# ATM90E32AS.net
KiCad netlist of a schematic drawn in Altium Designer
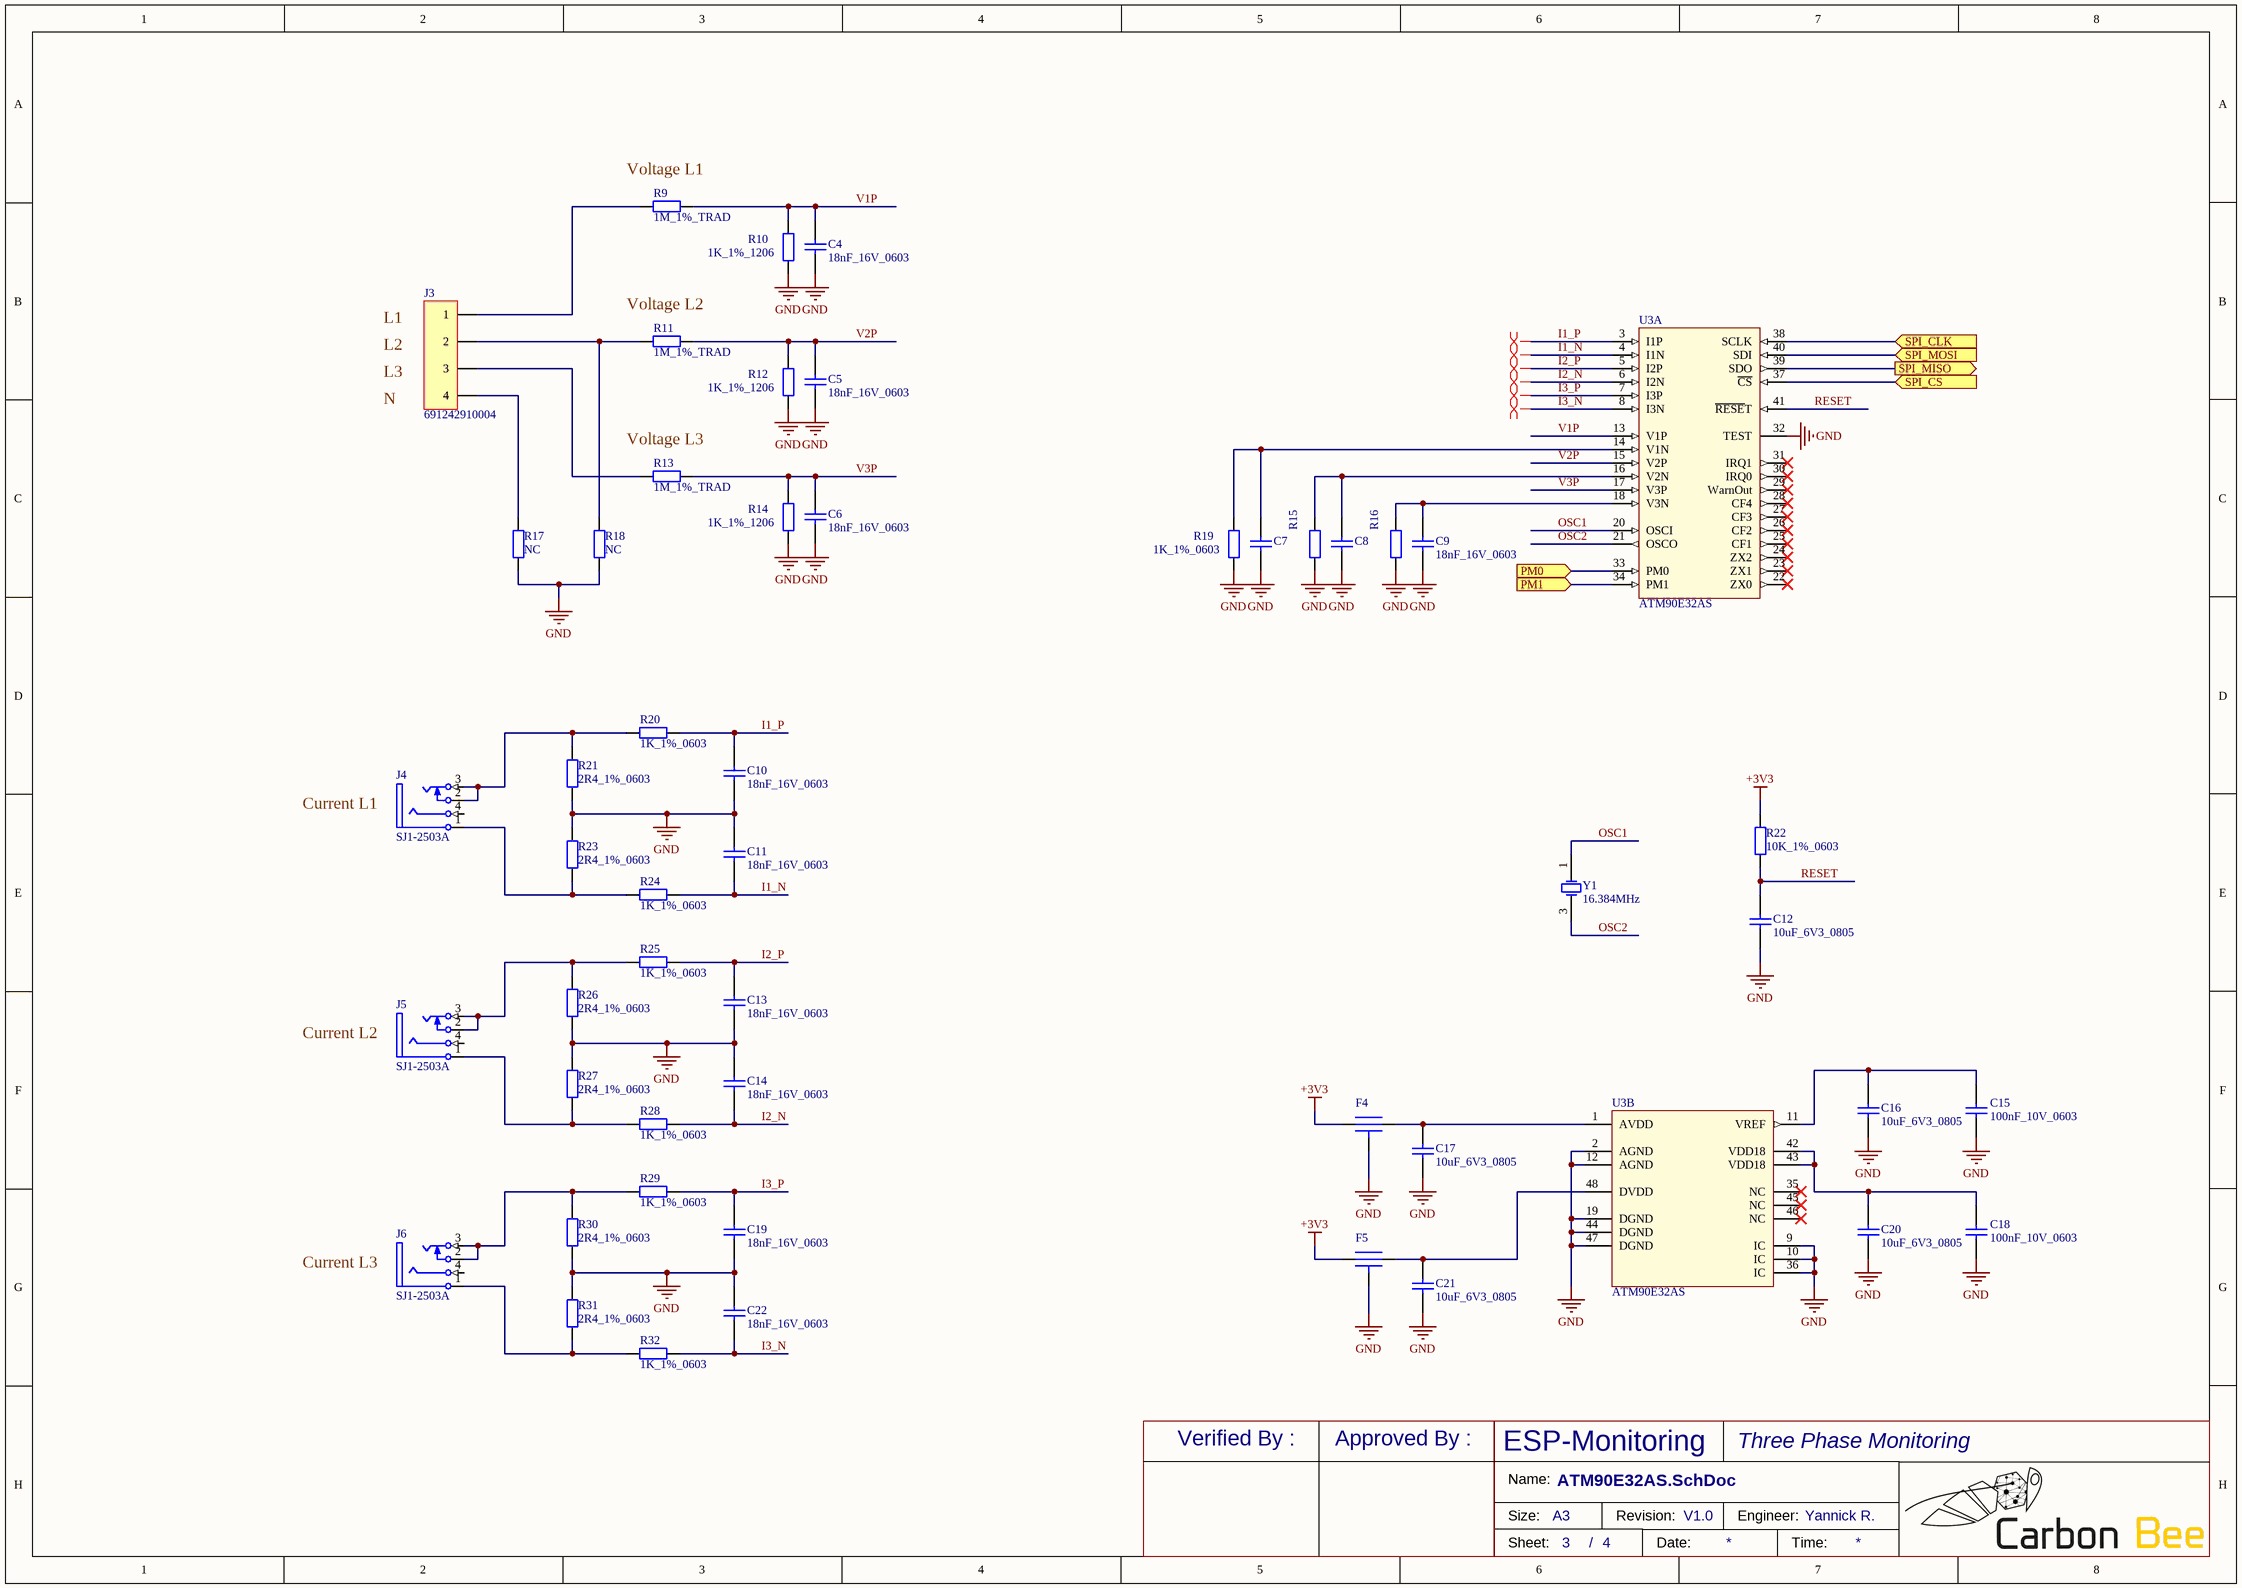
[diagram p0: ATM90E32AS.SchDoc]

(export (version "E")
  (design (tool "Eeschema 10.0.6"))
  (components
    (comp (ref "C4")
      (value "18nF_16V_0603")
      (footprint "C0603")
      (description "Capacitor")
      (fields (field (name "MF") "MULTICOMP") (field (name "MPN") "MC0603B183K160CT"))
      (libsource (lib "Common") (part "Cap"))
    )
    (comp (ref "C5")
      (value "18nF_16V_0603")
      (footprint "C0603")
      (description "Capacitor")
      (fields (field (name "MF") "MULTICOMP") (field (name "MPN") "MC0603B183K160CT"))
      (libsource (lib "Common") (part "Cap"))
    )
    (comp (ref "C6")
      (value "18nF_16V_0603")
      (footprint "C0603")
      (description "Capacitor")
      (fields (field (name "MF") "MULTICOMP") (field (name "MPN") "MC0603B183K160CT"))
      (libsource (lib "Common") (part "Cap"))
    )
    (comp (ref "C7")
      (value "18nF_16V_0603")
      (footprint "C0603")
      (description "Capacitor")
      (fields (field (name "MF") "MULTICOMP") (field (name "MPN") "MC0603B183K160CT"))
      (libsource (lib "Common") (part "Cap"))
    )
    (comp (ref "C8")
      (value "18nF_16V_0603")
      (footprint "C0603")
      (description "Capacitor")
      (fields (field (name "MF") "MULTICOMP") (field (name "MPN") "MC0603B183K160CT"))
      (libsource (lib "Common") (part "Cap"))
    )
    (comp (ref "C9")
      (value "18nF_16V_0603")
      (footprint "C0603")
      (description "Capacitor")
      (fields (field (name "MF") "MULTICOMP") (field (name "MPN") "MC0603B183K160CT"))
      (libsource (lib "Common") (part "Cap"))
    )
    (comp (ref "C10")
      (value "18nF_16V_0603")
      (footprint "C0603")
      (description "Capacitor")
      (fields (field (name "MF") "MULTICOMP") (field (name "MPN") "MC0603B183K160CT"))
      (libsource (lib "Common") (part "Cap"))
    )
    (comp (ref "C11")
      (value "18nF_16V_0603")
      (footprint "C0603")
      (description "Capacitor")
      (fields (field (name "MF") "MULTICOMP") (field (name "MPN") "MC0603B183K160CT"))
      (libsource (lib "Common") (part "Cap"))
    )
    (comp (ref "C12")
      (value "10uF_6V3_0805")
      (footprint "Common:C0805")
      (description "Capacitor")
      (fields (field (name "MF") " MULTICOMP") (field (name "MPN") "MCTT21X106M6R3CT"))
      (libsource (lib "Common") (part "Cap"))
    )
    (comp (ref "C13")
      (value "18nF_16V_0603")
      (footprint "C0603")
      (description "Capacitor")
      (fields (field (name "MF") "MULTICOMP") (field (name "MPN") "MC0603B183K160CT"))
      (libsource (lib "Common") (part "Cap"))
    )
    (comp (ref "C14")
      (value "18nF_16V_0603")
      (footprint "C0603")
      (description "Capacitor")
      (fields (field (name "MF") "MULTICOMP") (field (name "MPN") "MC0603B183K160CT"))
      (libsource (lib "Common") (part "Cap"))
    )
    (comp (ref "C15")
      (value "100nF_10V_0603")
      (footprint "C0603")
      (description "Capacitor")
      (fields (field (name "MF") "MULTICOMP") (field (name "MPN") "MC0603B104K100CT"))
      (libsource (lib "Common") (part "Cap"))
    )
    (comp (ref "C16")
      (value "10uF_6V3_0805")
      (footprint "Common:C0805")
      (description "Capacitor")
      (fields (field (name "MF") " MULTICOMP") (field (name "MPN") "MCTT21X106M6R3CT"))
      (libsource (lib "Common") (part "Cap"))
    )
    (comp (ref "C17")
      (value "10uF_6V3_0805")
      (footprint "Common:C0805")
      (description "Capacitor")
      (fields (field (name "MF") " MULTICOMP") (field (name "MPN") "MCTT21X106M6R3CT"))
      (libsource (lib "Common") (part "Cap"))
    )
    (comp (ref "C18")
      (value "100nF_10V_0603")
      (footprint "C0603")
      (description "Capacitor")
      (fields (field (name "MF") "MULTICOMP") (field (name "MPN") "MC0603B104K100CT"))
      (libsource (lib "Common") (part "Cap"))
    )
    (comp (ref "C19")
      (value "18nF_16V_0603")
      (footprint "C0603")
      (description "Capacitor")
      (fields (field (name "MF") "MULTICOMP") (field (name "MPN") "MC0603B183K160CT"))
      (libsource (lib "Common") (part "Cap"))
    )
    (comp (ref "C20")
      (value "10uF_6V3_0805")
      (footprint "Common:C0805")
      (description "Capacitor")
      (fields (field (name "MF") " MULTICOMP") (field (name "MPN") "MCTT21X106M6R3CT"))
      (libsource (lib "Common") (part "Cap"))
    )
    (comp (ref "C21")
      (value "10uF_6V3_0805")
      (footprint "Common:C0805")
      (description "Capacitor")
      (fields (field (name "MF") " MULTICOMP") (field (name "MPN") "MCTT21X106M6R3CT"))
      (libsource (lib "Common") (part "Cap"))
    )
    (comp (ref "C22")
      (value "18nF_16V_0603")
      (footprint "C0603")
      (description "Capacitor")
      (fields (field (name "MF") "MULTICOMP") (field (name "MPN") "MC0603B183K160CT"))
      (libsource (lib "Common") (part "Cap"))
    )
    (comp (ref "F4")
      (value "EMI")
      (footprint "EMIFIL_0603")
      (description "FILTER CAP 0.1UF 2A 16V 0603")
      (fields (field (name "MF") "MURATA") (field (name "MPN") "NFM18PC104R1C3D"))
      (libsource (lib "Common") (part "EMIFIL_0603"))
    )
    (comp (ref "F5")
      (value "EMI")
      (footprint "EMIFIL_0603")
      (description "FILTER CAP 0.1UF 2A 16V 0603")
      (fields (field (name "MF") "MURATA") (field (name "MPN") "NFM18PC104R1C3D"))
      (libsource (lib "Common") (part "EMIFIL_0603"))
    )
    (comp (ref "J3")
      (value "691242910004")
      (footprint "691242910004")
      (description "Horizontal Cable Entry with Rising Cage Clamp, Serie 2429 - 7.5 mm")
      (fields (field (name "MF") "Wurth Elektronik"))
      (libsource (lib "WE_WR-TBL_Rising Cage System_7.50 mm_rev15b") (part "691242910004"))
    )
    (comp (ref "J4")
      (value "SJ1-2503A")
      (footprint "SJ1-2503A")
      (description "Jack Socket, 1/4\" [6.5mm], Thru-Hole, Vertical, 3-Conductor with Tip closed & Ring open")
      (fields (field (name "MF") "CUI Inc."))
      (libsource (lib "Miscellaneous Connectors") (part "Phonejack3 TN"))
    )
    (comp (ref "J5")
      (value "SJ1-2503A")
      (footprint "SJ1-2503A")
      (description "Jack Socket, 1/4\" [6.5mm], Thru-Hole, Vertical, 3-Conductor with Tip closed & Ring open")
      (fields (field (name "MF") "CUI Inc."))
      (libsource (lib "Miscellaneous Connectors") (part "Phonejack3 TN"))
    )
    (comp (ref "J6")
      (value "SJ1-2503A")
      (footprint "SJ1-2503A")
      (description "Jack Socket, 1/4\" [6.5mm], Thru-Hole, Vertical, 3-Conductor with Tip closed & Ring open")
      (fields (field (name "MF") "CUI Inc."))
      (libsource (lib "Miscellaneous Connectors") (part "Phonejack3 TN"))
    )
    (comp (ref "R9")
      (value "1M_1%_TRAD")
      (footprint "AXIAL-0.3")
      (description "Resistor")
      (fields (field (name "MF") "TT ELECTRONICS / WELWYN") (field (name "MPN") "MH25-1MJI"))
      (libsource (lib "") (part "RES_1"))
    )
    (comp (ref "R10")
      (value "1K_1%_1206")
      (footprint "R1206")
      (description "Resistor")
      (fields (field (name "MF") "MULTICOMP") (field (name "MPN") "MC0125W120651K"))
      (libsource (lib "") (part "RES_2"))
    )
    (comp (ref "R11")
      (value "1M_1%_TRAD")
      (footprint "AXIAL-0.3")
      (description "Resistor")
      (fields (field (name "MF") "TT ELECTRONICS / WELWYN") (field (name "MPN") "MH25-1MJI"))
      (libsource (lib "") (part "RES_1"))
    )
    (comp (ref "R12")
      (value "1K_1%_1206")
      (footprint "R1206")
      (description "Resistor")
      (fields (field (name "MF") "MULTICOMP") (field (name "MPN") "MC0125W120651K"))
      (libsource (lib "") (part "RES_2"))
    )
    (comp (ref "R13")
      (value "1M_1%_TRAD")
      (footprint "AXIAL-0.3")
      (description "Resistor")
      (fields (field (name "MF") "TT ELECTRONICS / WELWYN") (field (name "MPN") "MH25-1MJI"))
      (libsource (lib "") (part "RES_1"))
    )
    (comp (ref "R14")
      (value "1K_1%_1206")
      (footprint "R1206")
      (description "Resistor")
      (fields (field (name "MF") "MULTICOMP") (field (name "MPN") "MC0125W120651K"))
      (libsource (lib "") (part "RES_2"))
    )
    (comp (ref "R15")
      (value "1K_1%_0603")
      (footprint "R0603")
      (description "Resistor")
      (fields (field (name "MF") "VISHAY") (field (name "MPN") "CRCW06031K00FKEA"))
      (libsource (lib "") (part "RES_2"))
    )
    (comp (ref "R16")
      (value "1K_1%_0603")
      (footprint "R0603")
      (description "Resistor")
      (fields (field (name "MF") "VISHAY") (field (name "MPN") "CRCW06031K00FKEA"))
      (libsource (lib "") (part "RES_2"))
    )
    (comp (ref "R17")
      (value "NC")
      (footprint "AXIAL-0.4")
      (description "Resistor")
      (libsource (lib "") (part "RES_3"))
    )
    (comp (ref "R18")
      (value "NC")
      (footprint "AXIAL-0.4")
      (description "Resistor")
      (libsource (lib "") (part "RES_3"))
    )
    (comp (ref "R19")
      (value "1K_1%_0603")
      (footprint "R0603")
      (description "Resistor")
      (fields (field (name "MF") "VISHAY") (field (name "MPN") "CRCW06031K00FKEA"))
      (libsource (lib "") (part "RES_2"))
    )
    (comp (ref "R20")
      (value "1K_1%_0603")
      (footprint "R0603")
      (description "Resistor")
      (fields (field (name "MF") "VISHAY") (field (name "MPN") "CRCW06031K00FKEA"))
      (libsource (lib "") (part "RES_1"))
    )
    (comp (ref "R21")
      (value "2R4_1%_0603")
      (footprint "R0603")
      (description "Resistor")
      (fields (field (name "MF") "WALSIN") (field (name "MPN") "WR06W2R40FTL"))
      (libsource (lib "") (part "RES_3"))
    )
    (comp (ref "R22")
      (value "10K_1%_0603")
      (footprint "R0603")
      (description "Resistor")
      (fields (field (name "MPN") "MCWR06X1002FTL") (field (name "MF") "MULTICOMP"))
      (libsource (lib "Common") (part "RES"))
    )
    (comp (ref "R23")
      (value "2R4_1%_0603")
      (footprint "R0603")
      (description "Resistor")
      (fields (field (name "MF") "WALSIN") (field (name "MPN") "WR06W2R40FTL"))
      (libsource (lib "Common") (part "RES"))
    )
    (comp (ref "R24")
      (value "1K_1%_0603")
      (footprint "R0603")
      (description "Resistor")
      (fields (field (name "MF") "VISHAY") (field (name "MPN") "CRCW06031K00FKEA"))
      (libsource (lib "") (part "RES_3"))
    )
    (comp (ref "R25")
      (value "1K_1%_0603")
      (footprint "R0603")
      (description "Resistor")
      (fields (field (name "MF") "VISHAY") (field (name "MPN") "CRCW06031K00FKEA"))
      (libsource (lib "") (part "RES_1"))
    )
    (comp (ref "R26")
      (value "2R4_1%_0603")
      (footprint "R0603")
      (description "Resistor")
      (fields (field (name "MF") "WALSIN") (field (name "MPN") "WR06W2R40FTL"))
      (libsource (lib "") (part "RES_3"))
    )
    (comp (ref "R27")
      (value "2R4_1%_0603")
      (footprint "R0603")
      (description "Resistor")
      (fields (field (name "MF") "WALSIN") (field (name "MPN") "WR06W2R40FTL"))
      (libsource (lib "Common") (part "RES"))
    )
    (comp (ref "R28")
      (value "1K_1%_0603")
      (footprint "R0603")
      (description "Resistor")
      (fields (field (name "MF") "VISHAY") (field (name "MPN") "CRCW06031K00FKEA"))
      (libsource (lib "") (part "RES_3"))
    )
    (comp (ref "R29")
      (value "1K_1%_0603")
      (footprint "R0603")
      (description "Resistor")
      (fields (field (name "MF") "VISHAY") (field (name "MPN") "CRCW06031K00FKEA"))
      (libsource (lib "") (part "RES_1"))
    )
    (comp (ref "R30")
      (value "2R4_1%_0603")
      (footprint "R0603")
      (description "Resistor")
      (fields (field (name "MF") "WALSIN") (field (name "MPN") "WR06W2R40FTL"))
      (libsource (lib "") (part "RES_3"))
    )
    (comp (ref "R31")
      (value "2R4_1%_0603")
      (footprint "R0603")
      (description "Resistor")
      (fields (field (name "MF") "WALSIN") (field (name "MPN") "WR06W2R40FTL"))
      (libsource (lib "Common") (part "RES"))
    )
    (comp (ref "R32")
      (value "1K_1%_0603")
      (footprint "R0603")
      (description "Resistor")
      (fields (field (name "MF") "VISHAY") (field (name "MPN") "CRCW06031K00FKEA"))
      (libsource (lib "") (part "RES_3"))
    )
    (comp (ref "U3")
      (value "ATM90E32AS")
      (footprint "TQFP48")
      (description "Enhanced Poly-Phase High-Performance Wide-Span Energy Metering IC")
      (fields (field (name "MF") "MICROCHIP") (field (name "MPN") "ATM90E32AS-AU-R"))
      (libsource (lib "Common") (part "ATM90E32AS"))
    )
    (comp (ref "Y1")
      (value "16.384MHz")
      (footprint "OSC_3.2X2.5")
      (description "Crystal Oscillator")
      (fields (field (name "MF") "MULTICOMP") (field (name "MPN") "MCSJK-7U-16.384-10-30-80-B-30"))
      (libsource (lib "Miscellaneous Devices") (part "XTAL"))
    )
  )
  (nets
    (net (code "1") (name "+3V3") (class "Default")
      (node (ref "F4") (pin "2") (pinfunction "2_2") (pintype "passive"))
      (node (ref "F5") (pin "2") (pinfunction "2_2") (pintype "passive"))
      (node (ref "R22") (pin "2") (pinfunction "2_2") (pintype "passive"))
    )
    (net (code "2") (name "/I1_N") (class "Default")
      (node (ref "C11") (pin "2") (pinfunction "2_2") (pintype "passive"))
      (node (ref "R24") (pin "1") (pinfunction "1_1") (pintype "passive"))
      (node (ref "U3") (pin "4") (pinfunction "I1N_4") (pintype "input"))
    )
    (net (code "3") (name "/I1_P") (class "Default")
      (node (ref "C10") (pin "2") (pinfunction "2_2") (pintype "passive"))
      (node (ref "R20") (pin "1") (pinfunction "1_1") (pintype "passive"))
      (node (ref "U3") (pin "3") (pinfunction "I1P_3") (pintype "input"))
    )
    (net (code "4") (name "/I2_N") (class "Default")
      (node (ref "C14") (pin "2") (pinfunction "2_2") (pintype "passive"))
      (node (ref "R28") (pin "1") (pinfunction "1_1") (pintype "passive"))
      (node (ref "U3") (pin "6") (pinfunction "I2N_6") (pintype "input"))
    )
    (net (code "5") (name "/I2_P") (class "Default")
      (node (ref "C13") (pin "2") (pinfunction "2_2") (pintype "passive"))
      (node (ref "R25") (pin "1") (pinfunction "1_1") (pintype "passive"))
      (node (ref "U3") (pin "5") (pinfunction "I2P_5") (pintype "input"))
    )
    (net (code "6") (name "/I3_N") (class "Default")
      (node (ref "C22") (pin "2") (pinfunction "2_2") (pintype "passive"))
      (node (ref "R32") (pin "1") (pinfunction "1_1") (pintype "passive"))
      (node (ref "U3") (pin "8") (pinfunction "I3N_8") (pintype "input"))
    )
    (net (code "7") (name "/I3_P") (class "Default")
      (node (ref "C19") (pin "2") (pinfunction "2_2") (pintype "passive"))
      (node (ref "R29") (pin "1") (pinfunction "1_1") (pintype "passive"))
      (node (ref "U3") (pin "7") (pinfunction "I3P_7") (pintype "input"))
    )
    (net (code "8") (name "/OSC1") (class "Default")
      (node (ref "U3") (pin "20") (pinfunction "OSCI_20") (pintype "input"))
      (node (ref "Y1") (pin "1") (pinfunction "OSC1_1") (pintype "passive"))
    )
    (net (code "9") (name "/OSC2") (class "Default")
      (node (ref "U3") (pin "21") (pinfunction "OSCO_21") (pintype "output"))
      (node (ref "Y1") (pin "3") (pinfunction "OSC2_3") (pintype "passive"))
    )
    (net (code "10") (name "/PM0") (class "Default")
      (node (ref "U3") (pin "33") (pinfunction "PM0_33") (pintype "input"))
    )
    (net (code "11") (name "/PM1") (class "Default")
      (node (ref "U3") (pin "34") (pinfunction "PM1_34") (pintype "input"))
    )
    (net (code "12") (name "/RESET") (class "Default")
      (node (ref "C12") (pin "2") (pinfunction "2_2") (pintype "passive"))
      (node (ref "R22") (pin "1") (pinfunction "1_1") (pintype "passive"))
      (node (ref "U3") (pin "41") (pinfunction "~{RESE}T_41") (pintype "input"))
    )
    (net (code "13") (name "/SPI_CLK") (class "Default")
      (node (ref "U3") (pin "38") (pinfunction "SCLK_38") (pintype "input"))
    )
    (net (code "14") (name "/SPI_CS") (class "Default")
      (node (ref "U3") (pin "37") (pinfunction "~{CS}_37") (pintype "input"))
    )
    (net (code "15") (name "/SPI_MISO") (class "Default")
      (node (ref "U3") (pin "39") (pinfunction "SDO_39") (pintype "output"))
    )
    (net (code "16") (name "/SPI_MOSI") (class "Default")
      (node (ref "U3") (pin "40") (pinfunction "SDI_40") (pintype "input"))
    )
    (net (code "17") (name "/V1P") (class "Default")
      (node (ref "C4") (pin "2") (pinfunction "2_2") (pintype "passive"))
      (node (ref "R10") (pin "2") (pinfunction "2_2") (pintype "passive"))
      (node (ref "R9") (pin "1") (pinfunction "1_1") (pintype "passive"))
      (node (ref "U3") (pin "13") (pinfunction "V1P_13") (pintype "input"))
    )
    (net (code "18") (name "/V2P") (class "Default")
      (node (ref "C5") (pin "2") (pinfunction "2_2") (pintype "passive"))
      (node (ref "R11") (pin "1") (pinfunction "1_1") (pintype "passive"))
      (node (ref "R12") (pin "2") (pinfunction "2_2") (pintype "passive"))
      (node (ref "U3") (pin "15") (pinfunction "V2P_15") (pintype "input"))
    )
    (net (code "19") (name "/V3P") (class "Default")
      (node (ref "C6") (pin "2") (pinfunction "2_2") (pintype "passive"))
      (node (ref "R13") (pin "1") (pinfunction "1_1") (pintype "passive"))
      (node (ref "R14") (pin "2") (pinfunction "2_2") (pintype "passive"))
      (node (ref "U3") (pin "17") (pinfunction "V3P_17") (pintype "input"))
    )
    (net (code "20") (name "GND") (class "Default")
      (node (ref "C10") (pin "1") (pinfunction "1_1") (pintype "passive"))
      (node (ref "C11") (pin "1") (pinfunction "1_1") (pintype "passive"))
      (node (ref "C12") (pin "1") (pinfunction "1_1") (pintype "passive"))
      (node (ref "C13") (pin "1") (pinfunction "1_1") (pintype "passive"))
      (node (ref "C14") (pin "1") (pinfunction "1_1") (pintype "passive"))
      (node (ref "C15") (pin "1") (pinfunction "1_1") (pintype "passive"))
      (node (ref "C16") (pin "1") (pinfunction "1_1") (pintype "passive"))
      (node (ref "C17") (pin "1") (pinfunction "1_1") (pintype "passive"))
      (node (ref "C18") (pin "1") (pinfunction "1_1") (pintype "passive"))
      (node (ref "C19") (pin "1") (pinfunction "1_1") (pintype "passive"))
      (node (ref "C20") (pin "1") (pinfunction "1_1") (pintype "passive"))
      (node (ref "C21") (pin "1") (pinfunction "1_1") (pintype "passive"))
      (node (ref "C22") (pin "1") (pinfunction "1_1") (pintype "passive"))
      (node (ref "C4") (pin "1") (pinfunction "1_1") (pintype "passive"))
      (node (ref "C5") (pin "1") (pinfunction "1_1") (pintype "passive"))
      (node (ref "C6") (pin "1") (pinfunction "1_1") (pintype "passive"))
      (node (ref "C7") (pin "1") (pinfunction "1_1") (pintype "passive"))
      (node (ref "C8") (pin "1") (pinfunction "1_1") (pintype "passive"))
      (node (ref "C9") (pin "1") (pinfunction "1_1") (pintype "passive"))
      (node (ref "F4") (pin "GND") (pinfunction "GND_GND") (pintype "passive"))
      (node (ref "F5") (pin "GND") (pinfunction "GND_GND") (pintype "passive"))
      (node (ref "R10") (pin "1") (pinfunction "1_1") (pintype "passive"))
      (node (ref "R12") (pin "1") (pinfunction "1_1") (pintype "passive"))
      (node (ref "R14") (pin "1") (pinfunction "1_1") (pintype "passive"))
      (node (ref "R15") (pin "1") (pinfunction "1_1") (pintype "passive"))
      (node (ref "R16") (pin "1") (pinfunction "1_1") (pintype "passive"))
      (node (ref "R17") (pin "2") (pinfunction "2_2") (pintype "passive"))
      (node (ref "R18") (pin "2") (pinfunction "2_2") (pintype "passive"))
      (node (ref "R19") (pin "1") (pinfunction "1_1") (pintype "passive"))
      (node (ref "R21") (pin "2") (pinfunction "2_2") (pintype "passive"))
      (node (ref "R23") (pin "2") (pinfunction "2_2") (pintype "passive"))
      (node (ref "R26") (pin "2") (pinfunction "2_2") (pintype "passive"))
      (node (ref "R27") (pin "2") (pinfunction "2_2") (pintype "passive"))
      (node (ref "R30") (pin "2") (pinfunction "2_2") (pintype "passive"))
      (node (ref "R31") (pin "2") (pinfunction "2_2") (pintype "passive"))
      (node (ref "U3") (pin "10") (pinfunction "IC_10") (pintype "passive"))
      (node (ref "U3") (pin "12") (pinfunction "AGND_12") (pintype "passive"))
      (node (ref "U3") (pin "19") (pinfunction "DGND_19") (pintype "passive"))
      (node (ref "U3") (pin "2") (pinfunction "AGND_2") (pintype "passive"))
      (node (ref "U3") (pin "32") (pinfunction "TEST_32") (pintype "passive"))
      (node (ref "U3") (pin "36") (pinfunction "IC_36") (pintype "passive"))
      (node (ref "U3") (pin "44") (pinfunction "DGND_44") (pintype "passive"))
      (node (ref "U3") (pin "47") (pinfunction "DGND_47") (pintype "passive"))
      (node (ref "U3") (pin "9") (pinfunction "IC_9") (pintype "passive"))
    )
    (net (code "21") (name "Net-(C18-Pad2)") (class "Default")
      (node (ref "C18") (pin "2") (pinfunction "2_2") (pintype "passive"))
      (node (ref "C20") (pin "2") (pinfunction "2_2") (pintype "passive"))
      (node (ref "U3") (pin "42") (pinfunction "VDD18_42") (pintype "passive"))
      (node (ref "U3") (pin "43") (pinfunction "VDD18_43") (pintype "passive"))
    )
    (net (code "22") (name "Net-(J3-Pad1)") (class "Default")
      (node (ref "J3") (pin "1") (pinfunction "1_1") (pintype "passive"))
      (node (ref "R9") (pin "2") (pinfunction "2_2") (pintype "passive"))
    )
    (net (code "23") (name "Net-(J3-Pad2)") (class "Default")
      (node (ref "J3") (pin "2") (pinfunction "2_2") (pintype "passive"))
      (node (ref "R11") (pin "2") (pinfunction "2_2") (pintype "passive"))
      (node (ref "R18") (pin "1") (pinfunction "1_1") (pintype "passive"))
    )
    (net (code "24") (name "Net-(J3-Pad3)") (class "Default")
      (node (ref "J3") (pin "3") (pinfunction "3_3") (pintype "passive"))
      (node (ref "R13") (pin "2") (pinfunction "2_2") (pintype "passive"))
    )
    (net (code "25") (name "Net-(J3-Pad4)") (class "Default")
      (node (ref "J3") (pin "4") (pinfunction "4_4") (pintype "passive"))
      (node (ref "R17") (pin "1") (pinfunction "1_1") (pintype "passive"))
    )
    (net (code "26") (name "Net-(J4-S)") (class "Default")
      (node (ref "J4") (pin "1") (pinfunction "S_1") (pintype "power_in"))
      (node (ref "R23") (pin "1") (pinfunction "1_1") (pintype "passive"))
      (node (ref "R24") (pin "2") (pinfunction "2_2") (pintype "passive"))
    )
    (net (code "27") (name "Net-(J4-T)") (class "Default")
      (node (ref "J4") (pin "2") (pinfunction "TN_2") (pintype "passive"))
      (node (ref "J4") (pin "3") (pinfunction "T_3") (pintype "input"))
      (node (ref "R20") (pin "2") (pinfunction "2_2") (pintype "passive"))
      (node (ref "R21") (pin "1") (pinfunction "1_1") (pintype "passive"))
    )
    (net (code "28") (name "Net-(J5-S)") (class "Default")
      (node (ref "J5") (pin "1") (pinfunction "S_1") (pintype "power_in"))
      (node (ref "R27") (pin "1") (pinfunction "1_1") (pintype "passive"))
      (node (ref "R28") (pin "2") (pinfunction "2_2") (pintype "passive"))
    )
    (net (code "29") (name "Net-(J5-T)") (class "Default")
      (node (ref "J5") (pin "2") (pinfunction "TN_2") (pintype "passive"))
      (node (ref "J5") (pin "3") (pinfunction "T_3") (pintype "input"))
      (node (ref "R25") (pin "2") (pinfunction "2_2") (pintype "passive"))
      (node (ref "R26") (pin "1") (pinfunction "1_1") (pintype "passive"))
    )
    (net (code "30") (name "Net-(J6-S)") (class "Default")
      (node (ref "J6") (pin "1") (pinfunction "S_1") (pintype "power_in"))
      (node (ref "R31") (pin "1") (pinfunction "1_1") (pintype "passive"))
      (node (ref "R32") (pin "2") (pinfunction "2_2") (pintype "passive"))
    )
    (net (code "31") (name "Net-(J6-T)") (class "Default")
      (node (ref "J6") (pin "2") (pinfunction "TN_2") (pintype "passive"))
      (node (ref "J6") (pin "3") (pinfunction "T_3") (pintype "input"))
      (node (ref "R29") (pin "2") (pinfunction "2_2") (pintype "passive"))
      (node (ref "R30") (pin "1") (pinfunction "1_1") (pintype "passive"))
    )
    (net (code "32") (name "Net-(U3A-V1N)") (class "Default")
      (node (ref "C7") (pin "2") (pinfunction "2_2") (pintype "passive"))
      (node (ref "R19") (pin "2") (pinfunction "2_2") (pintype "passive"))
      (node (ref "U3") (pin "14") (pinfunction "V1N_14") (pintype "input"))
    )
    (net (code "33") (name "Net-(U3A-V2N)") (class "Default")
      (node (ref "C8") (pin "2") (pinfunction "2_2") (pintype "passive"))
      (node (ref "R15") (pin "2") (pinfunction "2_2") (pintype "passive"))
      (node (ref "U3") (pin "16") (pinfunction "V2N_16") (pintype "input"))
    )
    (net (code "34") (name "Net-(U3A-V3N)") (class "Default")
      (node (ref "C9") (pin "2") (pinfunction "2_2") (pintype "passive"))
      (node (ref "R16") (pin "2") (pinfunction "2_2") (pintype "passive"))
      (node (ref "U3") (pin "18") (pinfunction "V3N_18") (pintype "input"))
    )
    (net (code "35") (name "Net-(U3B-AVDD)") (class "Default")
      (node (ref "C17") (pin "2") (pinfunction "2_2") (pintype "passive"))
      (node (ref "F4") (pin "1") (pinfunction "1_1") (pintype "passive"))
      (node (ref "U3") (pin "1") (pinfunction "AVDD_1") (pintype "passive"))
    )
    (net (code "36") (name "Net-(U3B-DVDD)") (class "Default")
      (node (ref "C21") (pin "2") (pinfunction "2_2") (pintype "passive"))
      (node (ref "F5") (pin "1") (pinfunction "1_1") (pintype "passive"))
      (node (ref "U3") (pin "48") (pinfunction "DVDD_48") (pintype "passive"))
    )
    (net (code "37") (name "Net-(U3B-VREF)") (class "Default")
      (node (ref "C15") (pin "2") (pinfunction "2_2") (pintype "passive"))
      (node (ref "C16") (pin "2") (pinfunction "2_2") (pintype "passive"))
      (node (ref "U3") (pin "11") (pinfunction "VREF_11") (pintype "output"))
    )
    (net (code "38") (name "unconnected-(J4-R-Pad4)") (class "Default")
      (node (ref "J4") (pin "4") (pinfunction "R_4") (pintype "input"))
    )
    (net (code "39") (name "unconnected-(J5-R-Pad4)") (class "Default")
      (node (ref "J5") (pin "4") (pinfunction "R_4") (pintype "input"))
    )
    (net (code "40") (name "unconnected-(J6-R-Pad4)") (class "Default")
      (node (ref "J6") (pin "4") (pinfunction "R_4") (pintype "input"))
    )
    (net (code "41") (name "unconnected-(U3A-CF1-Pad25)") (class "Default")
      (node (ref "U3") (pin "25") (pinfunction "CF1_25") (pintype "output+no_connect"))
    )
    (net (code "42") (name "unconnected-(U3A-CF2-Pad26)") (class "Default")
      (node (ref "U3") (pin "26") (pinfunction "CF2_26") (pintype "output+no_connect"))
    )
    (net (code "43") (name "unconnected-(U3A-CF3-Pad27)") (class "Default")
      (node (ref "U3") (pin "27") (pinfunction "CF3_27") (pintype "output+no_connect"))
    )
    (net (code "44") (name "unconnected-(U3A-CF4-Pad28)") (class "Default")
      (node (ref "U3") (pin "28") (pinfunction "CF4_28") (pintype "output+no_connect"))
    )
    (net (code "45") (name "unconnected-(U3A-IRQ0-Pad30)") (class "Default")
      (node (ref "U3") (pin "30") (pinfunction "IRQ0_30") (pintype "output+no_connect"))
    )
    (net (code "46") (name "unconnected-(U3A-IRQ1-Pad31)") (class "Default")
      (node (ref "U3") (pin "31") (pinfunction "IRQ1_31") (pintype "output+no_connect"))
    )
    (net (code "47") (name "unconnected-(U3A-WarnOut-Pad29)") (class "Default")
      (node (ref "U3") (pin "29") (pinfunction "WarnOut_29") (pintype "output+no_connect"))
    )
    (net (code "48") (name "unconnected-(U3A-ZX0-Pad22)") (class "Default")
      (node (ref "U3") (pin "22") (pinfunction "ZX0_22") (pintype "output+no_connect"))
    )
    (net (code "49") (name "unconnected-(U3A-ZX1-Pad23)") (class "Default")
      (node (ref "U3") (pin "23") (pinfunction "ZX1_23") (pintype "output+no_connect"))
    )
    (net (code "50") (name "unconnected-(U3A-ZX2-Pad24)") (class "Default")
      (node (ref "U3") (pin "24") (pinfunction "ZX2_24") (pintype "output+no_connect"))
    )
    (net (code "51") (name "unconnected-(U3B-NC-Pad35)") (class "Default")
      (node (ref "U3") (pin "35") (pinfunction "NC_35") (pintype "passive+no_connect"))
    )
    (net (code "52") (name "unconnected-(U3B-NC-Pad45)") (class "Default")
      (node (ref "U3") (pin "45") (pinfunction "NC_45") (pintype "passive+no_connect"))
    )
    (net (code "53") (name "unconnected-(U3B-NC-Pad46)") (class "Default")
      (node (ref "U3") (pin "46") (pinfunction "NC_46") (pintype "passive+no_connect"))
    )
  )
)
